# CATS-FAT-IMU.net
KiCad netlist of a schematic drawn in Altium Designer
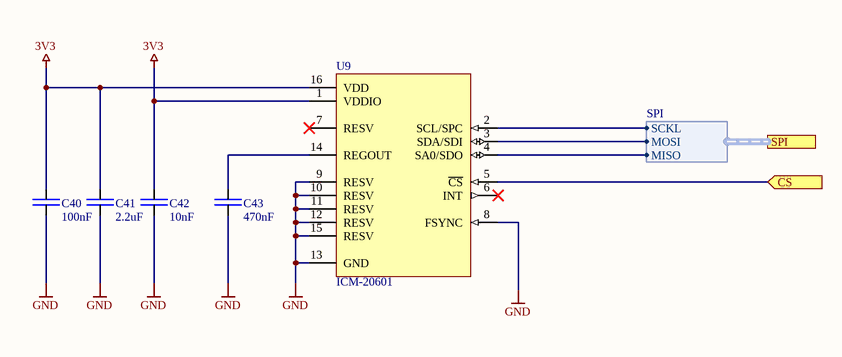
[diagram p0: CATS-FAT-IMU.SchDoc]

(export (version "E")
  (design (tool "Eeschema 10.0.6"))
  (components
    (comp (ref "C40")
      (value "100nF")
      (footprint "SMD Keramikkondensator 0603")
      (description "SMD Ceramic Capacitor E6")
      (libsource (lib "Ceramic Capacitors-E6") (part "E6 - 100nF"))
    )
    (comp (ref "C41")
      (value "2.2uF")
      (footprint "SMD Keramikkondensator 0603")
      (description "SMD Ceramic Capacitor E6")
      (libsource (lib "Ceramic Capacitors-E6") (part "E6 - 2.2uF"))
    )
    (comp (ref "C42")
      (value "10nF")
      (footprint "SMD Keramikkondensator 0603")
      (description "SMD Ceramic Capacitor E6")
      (libsource (lib "Ceramic Capacitors-E6") (part "E6 - 10nF"))
    )
    (comp (ref "C43")
      (value "470nF")
      (footprint "SMD Keramikkondensator 0603")
      (description "SMD Ceramic Capacitor E6")
      (libsource (lib "Ceramic Capacitors-E6") (part "E6 - 470nF"))
    )
    (comp (ref "U9")
      (value "ICM-20601")
      (footprint "SMD IC LGA-16 5/3")
      (description "World’s First Wide-Range 6-Axis MotionTracking Device for High Speed Applications")
      (libsource (lib "Sensors") (part "ICM-20601"))
    )
  )
  (nets
    (net (code "2") (name "/CS") (class "Default")
      (node (ref "U9") (pin "5") (pinfunction "~{CS}_5") (pintype "input"))
    )
    (net (code "3") (name "/MISO") (class "Default")
      (node (ref "U9") (pin "4") (pinfunction "SA0/SDO_4") (pintype "bidirectional"))
    )
    (net (code "4") (name "/MOSI") (class "Default")
      (node (ref "U9") (pin "3") (pinfunction "SDA/SDI_3") (pintype "bidirectional"))
    )
    (net (code "5") (name "/SCKL") (class "Default")
      (node (ref "U9") (pin "2") (pinfunction "SCL/SPC_2") (pintype "input"))
    )
    (net (code "7") (name "3V3") (class "Default")
      (node (ref "C40") (pin "2") (pinfunction "2_2") (pintype "passive"))
      (node (ref "C41") (pin "2") (pinfunction "2_2") (pintype "passive"))
      (node (ref "C42") (pin "2") (pinfunction "2_2") (pintype "passive"))
      (node (ref "U9") (pin "1") (pinfunction "VDDIO_1") (pintype "power_in"))
      (node (ref "U9") (pin "16") (pinfunction "VDD_16") (pintype "power_in"))
    )
    (net (code "8") (name "GND") (class "Default")
      (node (ref "C40") (pin "1") (pinfunction "1_1") (pintype "passive"))
      (node (ref "C41") (pin "1") (pinfunction "1_1") (pintype "passive"))
      (node (ref "C42") (pin "1") (pinfunction "1_1") (pintype "passive"))
      (node (ref "C43") (pin "1") (pinfunction "1_1") (pintype "passive"))
      (node (ref "U9") (pin "10") (pinfunction "RESV_10") (pintype "passive"))
      (node (ref "U9") (pin "11") (pinfunction "RESV_11") (pintype "passive"))
      (node (ref "U9") (pin "12") (pinfunction "RESV_12") (pintype "passive"))
      (node (ref "U9") (pin "13") (pinfunction "GND_13") (pintype "power_in"))
      (node (ref "U9") (pin "15") (pinfunction "RESV_15") (pintype "passive"))
      (node (ref "U9") (pin "8") (pinfunction "FSYNC_8") (pintype "input"))
      (node (ref "U9") (pin "9") (pinfunction "RESV_9") (pintype "passive"))
    )
    (net (code "9") (name "Net-(U9-REGOUT)") (class "Default")
      (node (ref "C43") (pin "2") (pinfunction "2_2") (pintype "passive"))
      (node (ref "U9") (pin "14") (pinfunction "REGOUT_14") (pintype "power_in"))
    )
    (net (code "10") (name "unconnected-(U9-INT-Pad6)") (class "Default")
      (node (ref "U9") (pin "6") (pinfunction "INT_6") (pintype "output+no_connect"))
    )
    (net (code "11") (name "unconnected-(U9-RESV-Pad7)") (class "Default")
      (node (ref "U9") (pin "7") (pinfunction "RESV_7") (pintype "passive+no_connect"))
    )
  )
)
